# DM0260_CCM.net
KiCad netlist of a schematic drawn in Altium Designer
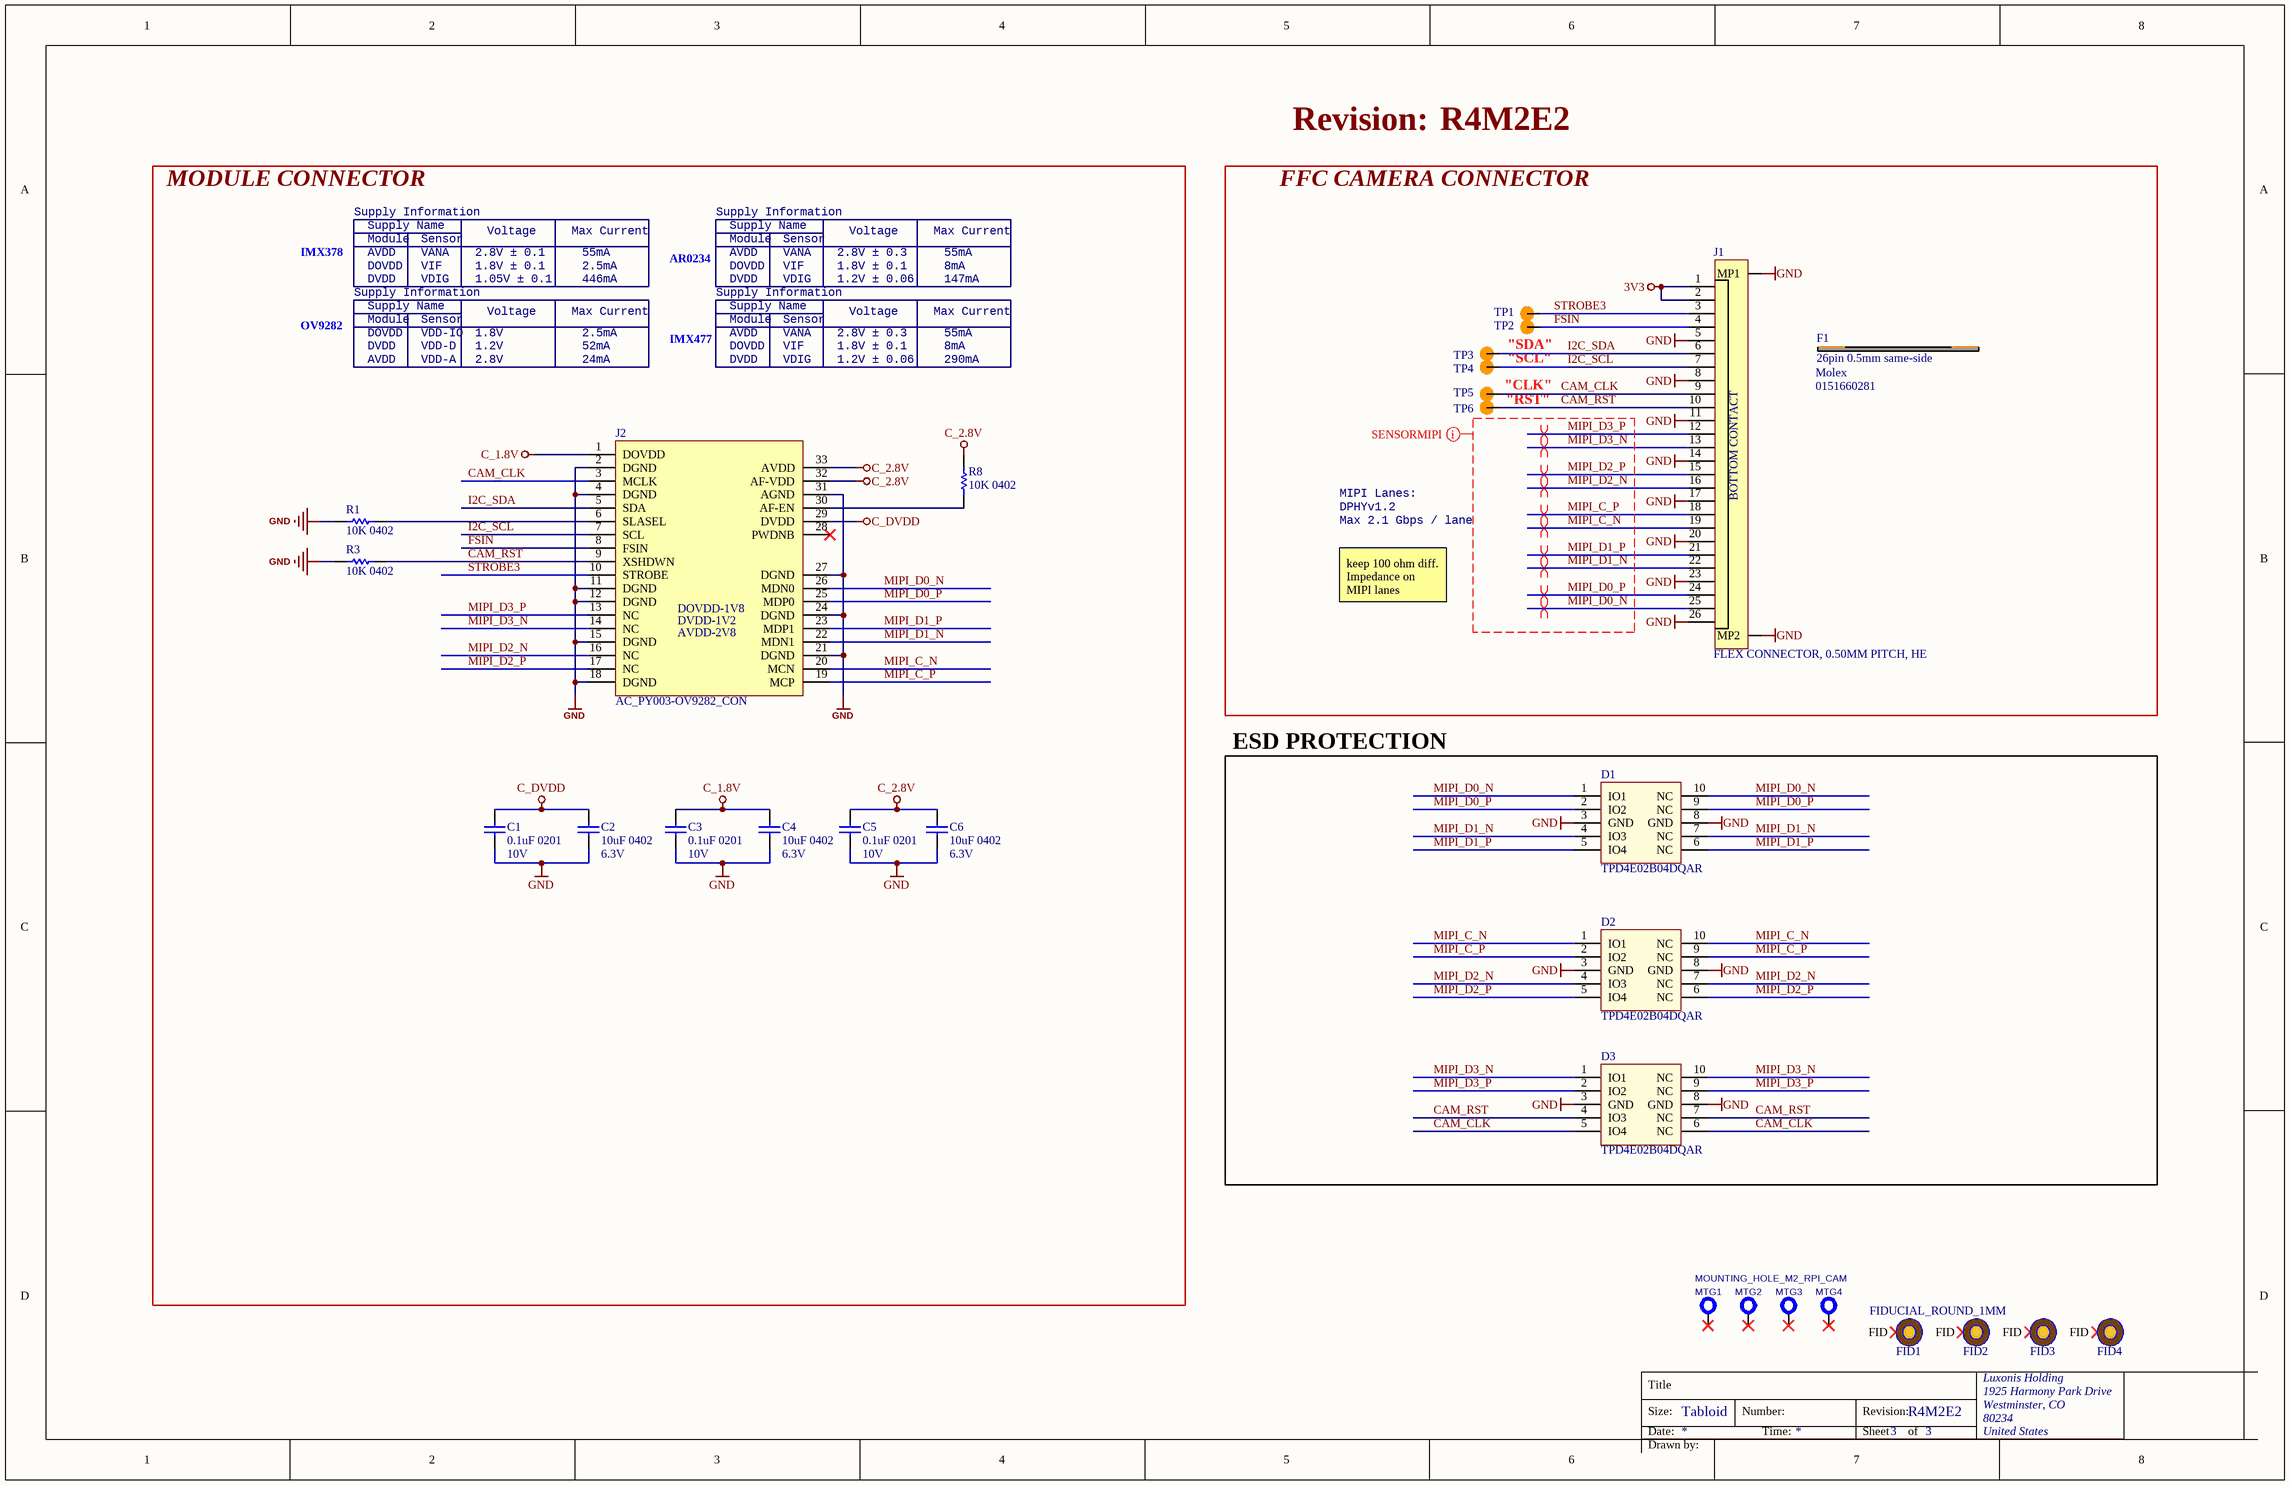
[diagram p0: DM0260_CCM.SchDoc]

(export (version "E")
  (design (tool "Eeschema 10.0.6"))
  (components
    (comp (ref "C1")
      (value "0.1uF 0201")
      (footprint "CAP_Altium_Vault_Generic:CAPC0201(0603)33_L")
      (description "CAP CER 0.1UF 10V X5R 0201")
      (fields (field (name "TOLERANCE") "10%") (field (name "VOLTAGE") "10V"))
      (libsource (lib "LuxonisMaster") (part "GRM033R61A104KE15D"))
    )
    (comp (ref "C2")
      (value "10uF 0402")
      (footprint "CAP_Altium_Vault_Generic:CAPC0402(1005)70_L")
      (description "CAP CER 10UF 6.3V X5R 0402 20%")
      (fields (field (name "TOLERANCE") "20%") (field (name "VOLTAGE RATING") "6.3V"))
      (libsource (lib "LuxonisMaster") (part "GRM155R60J106ME15D"))
    )
    (comp (ref "C3")
      (value "0.1uF 0201")
      (footprint "CAP_Altium_Vault_Generic:CAPC0201(0603)33_L")
      (description "CAP CER 0.1UF 10V X5R 0201")
      (fields (field (name "TOLERANCE") "10%") (field (name "VOLTAGE") "10V"))
      (libsource (lib "LuxonisMaster") (part "GRM033R61A104KE15D"))
    )
    (comp (ref "C4")
      (value "10uF 0402")
      (footprint "CAP_Altium_Vault_Generic:CAPC0402(1005)70_L")
      (description "CAP CER 10UF 6.3V X5R 0402 20%")
      (fields (field (name "TOLERANCE") "20%") (field (name "VOLTAGE RATING") "6.3V"))
      (libsource (lib "LuxonisMaster") (part "GRM155R60J106ME15D"))
    )
    (comp (ref "C5")
      (value "0.1uF 0201")
      (footprint "CAP_Altium_Vault_Generic:CAPC0201(0603)33_L")
      (description "CAP CER 0.1UF 10V X5R 0201")
      (fields (field (name "TOLERANCE") "10%") (field (name "VOLTAGE") "10V"))
      (libsource (lib "LuxonisMaster") (part "GRM033R61A104KE15D"))
    )
    (comp (ref "C6")
      (value "10uF 0402")
      (footprint "CAP_Altium_Vault_Generic:CAPC0402(1005)70_L")
      (description "CAP CER 10UF 6.3V X5R 0402 20%")
      (fields (field (name "TOLERANCE") "20%") (field (name "VOLTAGE RATING") "6.3V"))
      (libsource (lib "LuxonisMaster") (part "GRM155R60J106ME15D"))
    )
    (comp (ref "D1")
      (value "TPD4E02B04DQAR")
      (footprint "LuxonisMaster:TPD4E02B04DQAR")
      (libsource (lib "LuxonisMaster") (part "TPD4E02B04DQAR"))
    )
    (comp (ref "D2")
      (value "TPD4E02B04DQAR")
      (footprint "LuxonisMaster:TPD4E02B04DQAR")
      (libsource (lib "LuxonisMaster") (part "TPD4E02B04DQAR"))
    )
    (comp (ref "D3")
      (value "TPD4E02B04DQAR")
      (footprint "LuxonisMaster:TPD4E02B04DQAR")
      (libsource (lib "LuxonisMaster") (part "TPD4E02B04DQAR"))
    )
    (comp (ref "F1")
      (value "26pin 0.5mm same-side")
      (description "CABLE FFC 26POS 0.50MM 6\"")
      (fields
        (field (name "MANUFACTURER 1") "Molex")
        (field (name "MANUFACTURER PART NUMBER 1") "0151660281")
      )
      (libsource (lib "BG0249_R1M1E1") (part "0151660281"))
    )
    (comp (ref "FID1")
      (value "FIDUCIAL_ROUND_1MM")
      (footprint "LuxonisMaster:FIDUCIAL_ROUND_1MM")
      (description "Fiducial with various available footprints")
      (libsource (lib "LuxonisMaster") (part "FIDUCIAL"))
    )
    (comp (ref "FID2")
      (value "FIDUCIAL_ROUND_1MM")
      (footprint "LuxonisMaster:FIDUCIAL_ROUND_1MM")
      (description "Fiducial with various available footprints")
      (libsource (lib "LuxonisMaster") (part "FIDUCIAL"))
    )
    (comp (ref "FID3")
      (value "FIDUCIAL_ROUND_1MM")
      (footprint "LuxonisMaster:FIDUCIAL_ROUND_1MM")
      (description "Fiducial with various available footprints")
      (libsource (lib "LuxonisMaster") (part "FIDUCIAL"))
    )
    (comp (ref "FID4")
      (value "FIDUCIAL_ROUND_1MM")
      (footprint "LuxonisMaster:FIDUCIAL_ROUND_1MM")
      (description "Fiducial with various available footprints")
      (libsource (lib "LuxonisMaster") (part "FIDUCIAL"))
    )
    (comp (ref "J1")
      (value "FLEX CONNECTOR, 0.50MM PITCH, HE")
      (footprint "DM1090FFC:F32R-1A7H1-11026")
      (description "26 Position FFC, FPC Connector Contacts, Bottom 0.020\" (0.50mm) Surface Mount, Right Angle")
      (libsource (lib "DM1090FFC") (part "F32R-1A7H1-11026"))
    )
    (comp (ref "J2")
      (value "AC_PY003-OV9282_CON")
      (footprint "AC-PY003-OV9282")
      (description "FFC/FPC Connector, 33 Contact(s), 1 Row(s), Female, Right Angle, Surface Mount Terminal")
      (libsource (lib "Luxonis LLC") (part "AC_PY003-OV9282_CON"))
    )
    (comp (ref "MTG1")
      (value "MOUNTING_HOLE_M2_RPI_CAM")
      (footprint "LuxonisMaster:MOUNTING_HOLE_M2_RPI_CAM")
      (description "=CurrentFootprint")
      (libsource (lib "LuxonisMaster") (part "MP_Mounting-Holes"))
    )
    (comp (ref "MTG2")
      (value "MOUNTING_HOLE_M2_RPI_CAM")
      (footprint "LuxonisMaster:MOUNTING_HOLE_M2_RPI_CAM")
      (description "=CurrentFootprint")
      (libsource (lib "LuxonisMaster") (part "MP_Mounting-Holes"))
    )
    (comp (ref "MTG3")
      (value "MOUNTING_HOLE_M2_RPI_CAM")
      (footprint "LuxonisMaster:MOUNTING_HOLE_M2_RPI_CAM")
      (description "=CurrentFootprint")
      (libsource (lib "LuxonisMaster") (part "MP_Mounting-Holes"))
    )
    (comp (ref "MTG4")
      (value "MOUNTING_HOLE_M2_RPI_CAM")
      (footprint "LuxonisMaster:MOUNTING_HOLE_M2_RPI_CAM")
      (description "=CurrentFootprint")
      (libsource (lib "LuxonisMaster") (part "MP_Mounting-Holes"))
    )
    (comp (ref "R1")
      (value "10K 0402")
      (footprint "RES_Altium_Vault_Generic:RESC0402(1005)_L")
      (fields (field (name "TOLERANCE") "1%"))
      (libsource (lib "LuxonisMaster") (part "RC0402FR-1310KL"))
    )
    (comp (ref "R3")
      (value "10K 0402")
      (footprint "RES_Altium_Vault_Generic:RESC0402(1005)_L")
      (fields (field (name "TOLERANCE") "1%"))
      (libsource (lib "LuxonisMaster") (part "RC0402FR-1310KL"))
    )
    (comp (ref "R8")
      (value "10K 0402")
      (footprint "RES_Altium_Vault_Generic:RESC0402(1005)_L")
      (fields (field (name "TOLERANCE") "1%"))
      (libsource (lib "LuxonisMaster") (part "RC0402FR-1310KL"))
    )
    (comp (ref "TP1")
      (value "TP100_200_NS")
      (footprint "LuxonisMaster:TP100_200_NS")
      (libsource (lib "LuxonisMaster") (part "TEST_POINT"))
    )
    (comp (ref "TP2")
      (value "TP100_200_NS")
      (footprint "LuxonisMaster:TP100_200_NS")
      (libsource (lib "LuxonisMaster") (part "TEST_POINT"))
    )
    (comp (ref "TP3")
      (value "TP100_200_NS")
      (footprint "LuxonisMaster:TP100_200_NS")
      (libsource (lib "LuxonisMaster") (part "TEST_POINT"))
    )
    (comp (ref "TP4")
      (value "TP100_200_NS")
      (footprint "LuxonisMaster:TP100_200_NS")
      (libsource (lib "LuxonisMaster") (part "TEST_POINT"))
    )
    (comp (ref "TP5")
      (value "TP100_200_NS")
      (footprint "LuxonisMaster:TP100_200_NS")
      (libsource (lib "LuxonisMaster") (part "TEST_POINT"))
    )
    (comp (ref "TP6")
      (value "TP100_200_NS")
      (footprint "LuxonisMaster:TP100_200_NS")
      (libsource (lib "LuxonisMaster") (part "TEST_POINT"))
    )
  )
  (nets
    (net (code "1") (name "/CAM_CLK") (class "Default")
      (node (ref "D3") (pin "5") (pinfunction "IO4_5") (pintype "passive"))
      (node (ref "D3") (pin "6") (pinfunction "NC_6") (pintype "passive"))
      (node (ref "J1") (pin "9") (pinfunction "9_9") (pintype "passive"))
      (node (ref "J2") (pin "3") (pinfunction "MCLK_3") (pintype "passive"))
      (node (ref "TP5") (pin "1") (pintype "passive"))
    )
    (net (code "2") (name "/CAM_RST") (class "Default")
      (node (ref "D3") (pin "4") (pinfunction "IO3_4") (pintype "passive"))
      (node (ref "D3") (pin "7") (pinfunction "NC_7") (pintype "passive"))
      (node (ref "J1") (pin "10") (pinfunction "10_10") (pintype "passive"))
      (node (ref "J2") (pin "9") (pinfunction "XSHDWN_9") (pintype "passive"))
      (node (ref "R3") (pin "2") (pinfunction "2_2") (pintype "passive"))
      (node (ref "TP6") (pin "1") (pintype "passive"))
    )
    (net (code "3") (name "/FSIN") (class "Default")
      (node (ref "J1") (pin "4") (pinfunction "4_4") (pintype "passive"))
      (node (ref "J2") (pin "8") (pinfunction "FSIN_8") (pintype "passive"))
      (node (ref "TP2") (pin "1") (pintype "passive"))
    )
    (net (code "4") (name "/I2C_SCL") (class "Default")
      (node (ref "J1") (pin "7") (pinfunction "7_7") (pintype "passive"))
      (node (ref "J2") (pin "7") (pinfunction "SCL_7") (pintype "passive"))
      (node (ref "TP4") (pin "1") (pintype "passive"))
    )
    (net (code "5") (name "/I2C_SDA") (class "Default")
      (node (ref "J1") (pin "6") (pinfunction "6_6") (pintype "passive"))
      (node (ref "J2") (pin "5") (pinfunction "SDA_5") (pintype "passive"))
      (node (ref "TP3") (pin "1") (pintype "passive"))
    )
    (net (code "6") (name "/MIPI_C_N") (class "Default")
      (node (ref "D2") (pin "1") (pinfunction "IO1_1") (pintype "passive"))
      (node (ref "D2") (pin "10") (pinfunction "NC_10") (pintype "passive"))
      (node (ref "J1") (pin "19") (pinfunction "19_19") (pintype "passive"))
      (node (ref "J2") (pin "20") (pinfunction "MCN_20") (pintype "passive"))
    )
    (net (code "7") (name "/MIPI_C_P") (class "Default")
      (node (ref "D2") (pin "2") (pinfunction "IO2_2") (pintype "passive"))
      (node (ref "D2") (pin "9") (pinfunction "NC_9") (pintype "passive"))
      (node (ref "J1") (pin "18") (pinfunction "18_18") (pintype "passive"))
      (node (ref "J2") (pin "19") (pinfunction "MCP_19") (pintype "passive"))
    )
    (net (code "8") (name "/MIPI_D0_N") (class "Default")
      (node (ref "D1") (pin "1") (pinfunction "IO1_1") (pintype "passive"))
      (node (ref "D1") (pin "10") (pinfunction "NC_10") (pintype "passive"))
      (node (ref "J1") (pin "25") (pinfunction "25_25") (pintype "passive"))
      (node (ref "J2") (pin "26") (pinfunction "MDN0_26") (pintype "passive"))
    )
    (net (code "9") (name "/MIPI_D0_P") (class "Default")
      (node (ref "D1") (pin "2") (pinfunction "IO2_2") (pintype "passive"))
      (node (ref "D1") (pin "9") (pinfunction "NC_9") (pintype "passive"))
      (node (ref "J1") (pin "24") (pinfunction "24_24") (pintype "passive"))
      (node (ref "J2") (pin "25") (pinfunction "MDP0_25") (pintype "passive"))
    )
    (net (code "10") (name "/MIPI_D1_N") (class "Default")
      (node (ref "D1") (pin "4") (pinfunction "IO3_4") (pintype "passive"))
      (node (ref "D1") (pin "7") (pinfunction "NC_7") (pintype "passive"))
      (node (ref "J1") (pin "22") (pinfunction "22_22") (pintype "passive"))
      (node (ref "J2") (pin "22") (pinfunction "MDN1_22") (pintype "passive"))
    )
    (net (code "11") (name "/MIPI_D1_P") (class "Default")
      (node (ref "D1") (pin "5") (pinfunction "IO4_5") (pintype "passive"))
      (node (ref "D1") (pin "6") (pinfunction "NC_6") (pintype "passive"))
      (node (ref "J1") (pin "21") (pinfunction "21_21") (pintype "passive"))
      (node (ref "J2") (pin "23") (pinfunction "MDP1_23") (pintype "passive"))
    )
    (net (code "12") (name "/MIPI_D2_N") (class "Default")
      (node (ref "D2") (pin "4") (pinfunction "IO3_4") (pintype "passive"))
      (node (ref "D2") (pin "7") (pinfunction "NC_7") (pintype "passive"))
      (node (ref "J1") (pin "16") (pinfunction "16_16") (pintype "passive"))
      (node (ref "J2") (pin "16") (pinfunction "NC_16") (pintype "passive"))
    )
    (net (code "13") (name "/MIPI_D2_P") (class "Default")
      (node (ref "D2") (pin "5") (pinfunction "IO4_5") (pintype "passive"))
      (node (ref "D2") (pin "6") (pinfunction "NC_6") (pintype "passive"))
      (node (ref "J1") (pin "15") (pinfunction "15_15") (pintype "passive"))
      (node (ref "J2") (pin "17") (pinfunction "NC_17") (pintype "passive"))
    )
    (net (code "14") (name "/MIPI_D3_N") (class "Default")
      (node (ref "D3") (pin "1") (pinfunction "IO1_1") (pintype "passive"))
      (node (ref "D3") (pin "10") (pinfunction "NC_10") (pintype "passive"))
      (node (ref "J1") (pin "13") (pinfunction "13_13") (pintype "passive"))
      (node (ref "J2") (pin "14") (pinfunction "NC_14") (pintype "passive"))
    )
    (net (code "15") (name "/MIPI_D3_P") (class "Default")
      (node (ref "D3") (pin "2") (pinfunction "IO2_2") (pintype "passive"))
      (node (ref "D3") (pin "9") (pinfunction "NC_9") (pintype "passive"))
      (node (ref "J1") (pin "12") (pinfunction "12_12") (pintype "passive"))
      (node (ref "J2") (pin "13") (pinfunction "NC_13") (pintype "passive"))
    )
    (net (code "16") (name "/STROBE3") (class "Default")
      (node (ref "J1") (pin "3") (pinfunction "3_3") (pintype "passive"))
      (node (ref "J2") (pin "10") (pinfunction "STROBE_10") (pintype "passive"))
      (node (ref "TP1") (pin "1") (pintype "passive"))
    )
    (net (code "17") (name "3V3") (class "Default")
      (node (ref "J1") (pin "1") (pinfunction "1_1") (pintype "passive"))
      (node (ref "J1") (pin "2") (pinfunction "2_2") (pintype "passive"))
    )
    (net (code "18") (name "C_1.8V") (class "Default")
      (node (ref "C3") (pin "2") (pinfunction "2_2") (pintype "passive"))
      (node (ref "C4") (pin "2") (pinfunction "2_2") (pintype "passive"))
      (node (ref "J2") (pin "1") (pinfunction "DOVDD_1") (pintype "passive"))
    )
    (net (code "19") (name "C_2.8V") (class "Default")
      (node (ref "C5") (pin "2") (pinfunction "2_2") (pintype "passive"))
      (node (ref "C6") (pin "2") (pinfunction "2_2") (pintype "passive"))
      (node (ref "J2") (pin "32") (pinfunction "AF-VDD_32") (pintype "passive"))
      (node (ref "J2") (pin "33") (pinfunction "AVDD_33") (pintype "passive"))
      (node (ref "R8") (pin "2") (pinfunction "2_2") (pintype "passive"))
    )
    (net (code "20") (name "C_DVDD") (class "Default")
      (node (ref "C1") (pin "2") (pinfunction "2_2") (pintype "passive"))
      (node (ref "C2") (pin "2") (pinfunction "2_2") (pintype "passive"))
      (node (ref "J2") (pin "29") (pinfunction "DVDD_29") (pintype "passive"))
    )
    (net (code "21") (name "GND") (class "Default")
      (node (ref "C1") (pin "1") (pinfunction "1_1") (pintype "passive"))
      (node (ref "C2") (pin "1") (pinfunction "1_1") (pintype "passive"))
      (node (ref "C3") (pin "1") (pinfunction "1_1") (pintype "passive"))
      (node (ref "C4") (pin "1") (pinfunction "1_1") (pintype "passive"))
      (node (ref "C5") (pin "1") (pinfunction "1_1") (pintype "passive"))
      (node (ref "C6") (pin "1") (pinfunction "1_1") (pintype "passive"))
      (node (ref "D1") (pin "3") (pinfunction "GND_3") (pintype "passive"))
      (node (ref "D1") (pin "8") (pinfunction "GND_8") (pintype "passive"))
      (node (ref "D2") (pin "3") (pinfunction "GND_3") (pintype "passive"))
      (node (ref "D2") (pin "8") (pinfunction "GND_8") (pintype "passive"))
      (node (ref "D3") (pin "3") (pinfunction "GND_3") (pintype "passive"))
      (node (ref "D3") (pin "8") (pinfunction "GND_8") (pintype "passive"))
      (node (ref "J1") (pin "11") (pinfunction "11_11") (pintype "passive"))
      (node (ref "J1") (pin "14") (pinfunction "14_14") (pintype "passive"))
      (node (ref "J1") (pin "17") (pinfunction "17_17") (pintype "passive"))
      (node (ref "J1") (pin "20") (pinfunction "20_20") (pintype "passive"))
      (node (ref "J1") (pin "23") (pinfunction "23_23") (pintype "passive"))
      (node (ref "J1") (pin "26") (pinfunction "26_26") (pintype "passive"))
      (node (ref "J1") (pin "5") (pinfunction "5_5") (pintype "passive"))
      (node (ref "J1") (pin "8") (pinfunction "8_8") (pintype "passive"))
      (node (ref "J1") (pin "MP1") (pinfunction "MP1_MP1") (pintype "passive"))
      (node (ref "J1") (pin "MP2") (pinfunction "MP2_MP2") (pintype "passive"))
      (node (ref "J2") (pin "11") (pinfunction "DGND_11") (pintype "passive"))
      (node (ref "J2") (pin "12") (pinfunction "DGND_12") (pintype "passive"))
      (node (ref "J2") (pin "15") (pinfunction "DGND_15") (pintype "passive"))
      (node (ref "J2") (pin "18") (pinfunction "DGND_18") (pintype "passive"))
      (node (ref "J2") (pin "2") (pinfunction "DGND_2") (pintype "passive"))
      (node (ref "J2") (pin "21") (pinfunction "DGND_21") (pintype "passive"))
      (node (ref "J2") (pin "24") (pinfunction "DGND_24") (pintype "passive"))
      (node (ref "J2") (pin "27") (pinfunction "DGND_27") (pintype "passive"))
      (node (ref "J2") (pin "31") (pinfunction "AGND_31") (pintype "passive"))
      (node (ref "J2") (pin "4") (pinfunction "DGND_4") (pintype "passive"))
      (node (ref "R1") (pin "1") (pinfunction "1_1") (pintype "passive"))
      (node (ref "R3") (pin "1") (pinfunction "1_1") (pintype "passive"))
    )
    (net (code "22") (name "Net-(J2-AF-EN)") (class "Default")
      (node (ref "J2") (pin "30") (pinfunction "AF-EN_30") (pintype "passive"))
      (node (ref "R8") (pin "1") (pinfunction "1_1") (pintype "passive"))
    )
    (net (code "23") (name "Net-(J2-SLASEL)") (class "Default")
      (node (ref "J2") (pin "6") (pinfunction "SLASEL_6") (pintype "passive"))
      (node (ref "R1") (pin "2") (pinfunction "2_2") (pintype "passive"))
    )
    (net (code "24") (name "unconnected-(FID1-PadFID)") (class "Default")
      (node (ref "FID1") (pin "FID") (pinfunction "FID_FID") (pintype "input+no_connect"))
    )
    (net (code "25") (name "unconnected-(FID2-PadFID)") (class "Default")
      (node (ref "FID2") (pin "FID") (pinfunction "FID_FID") (pintype "input+no_connect"))
    )
    (net (code "26") (name "unconnected-(FID3-PadFID)") (class "Default")
      (node (ref "FID3") (pin "FID") (pinfunction "FID_FID") (pintype "input+no_connect"))
    )
    (net (code "27") (name "unconnected-(FID4-PadFID)") (class "Default")
      (node (ref "FID4") (pin "FID") (pinfunction "FID_FID") (pintype "input+no_connect"))
    )
    (net (code "28") (name "unconnected-(J2-PWDNB-Pad28)") (class "Default")
      (node (ref "J2") (pin "28") (pinfunction "PWDNB_28") (pintype "passive+no_connect"))
    )
    (net (code "29") (name "unconnected-(MTG1-Pad1)") (class "Default")
      (node (ref "MTG1") (pin "1") (pintype "passive+no_connect"))
    )
    (net (code "30") (name "unconnected-(MTG2-Pad1)") (class "Default")
      (node (ref "MTG2") (pin "1") (pintype "passive+no_connect"))
    )
    (net (code "31") (name "unconnected-(MTG3-Pad1)") (class "Default")
      (node (ref "MTG3") (pin "1") (pintype "passive+no_connect"))
    )
    (net (code "32") (name "unconnected-(MTG4-Pad1)") (class "Default")
      (node (ref "MTG4") (pin "1") (pintype "passive+no_connect"))
    )
  )
)
